# M1091A.net
KiCad netlist of a schematic drawn in EAGLE
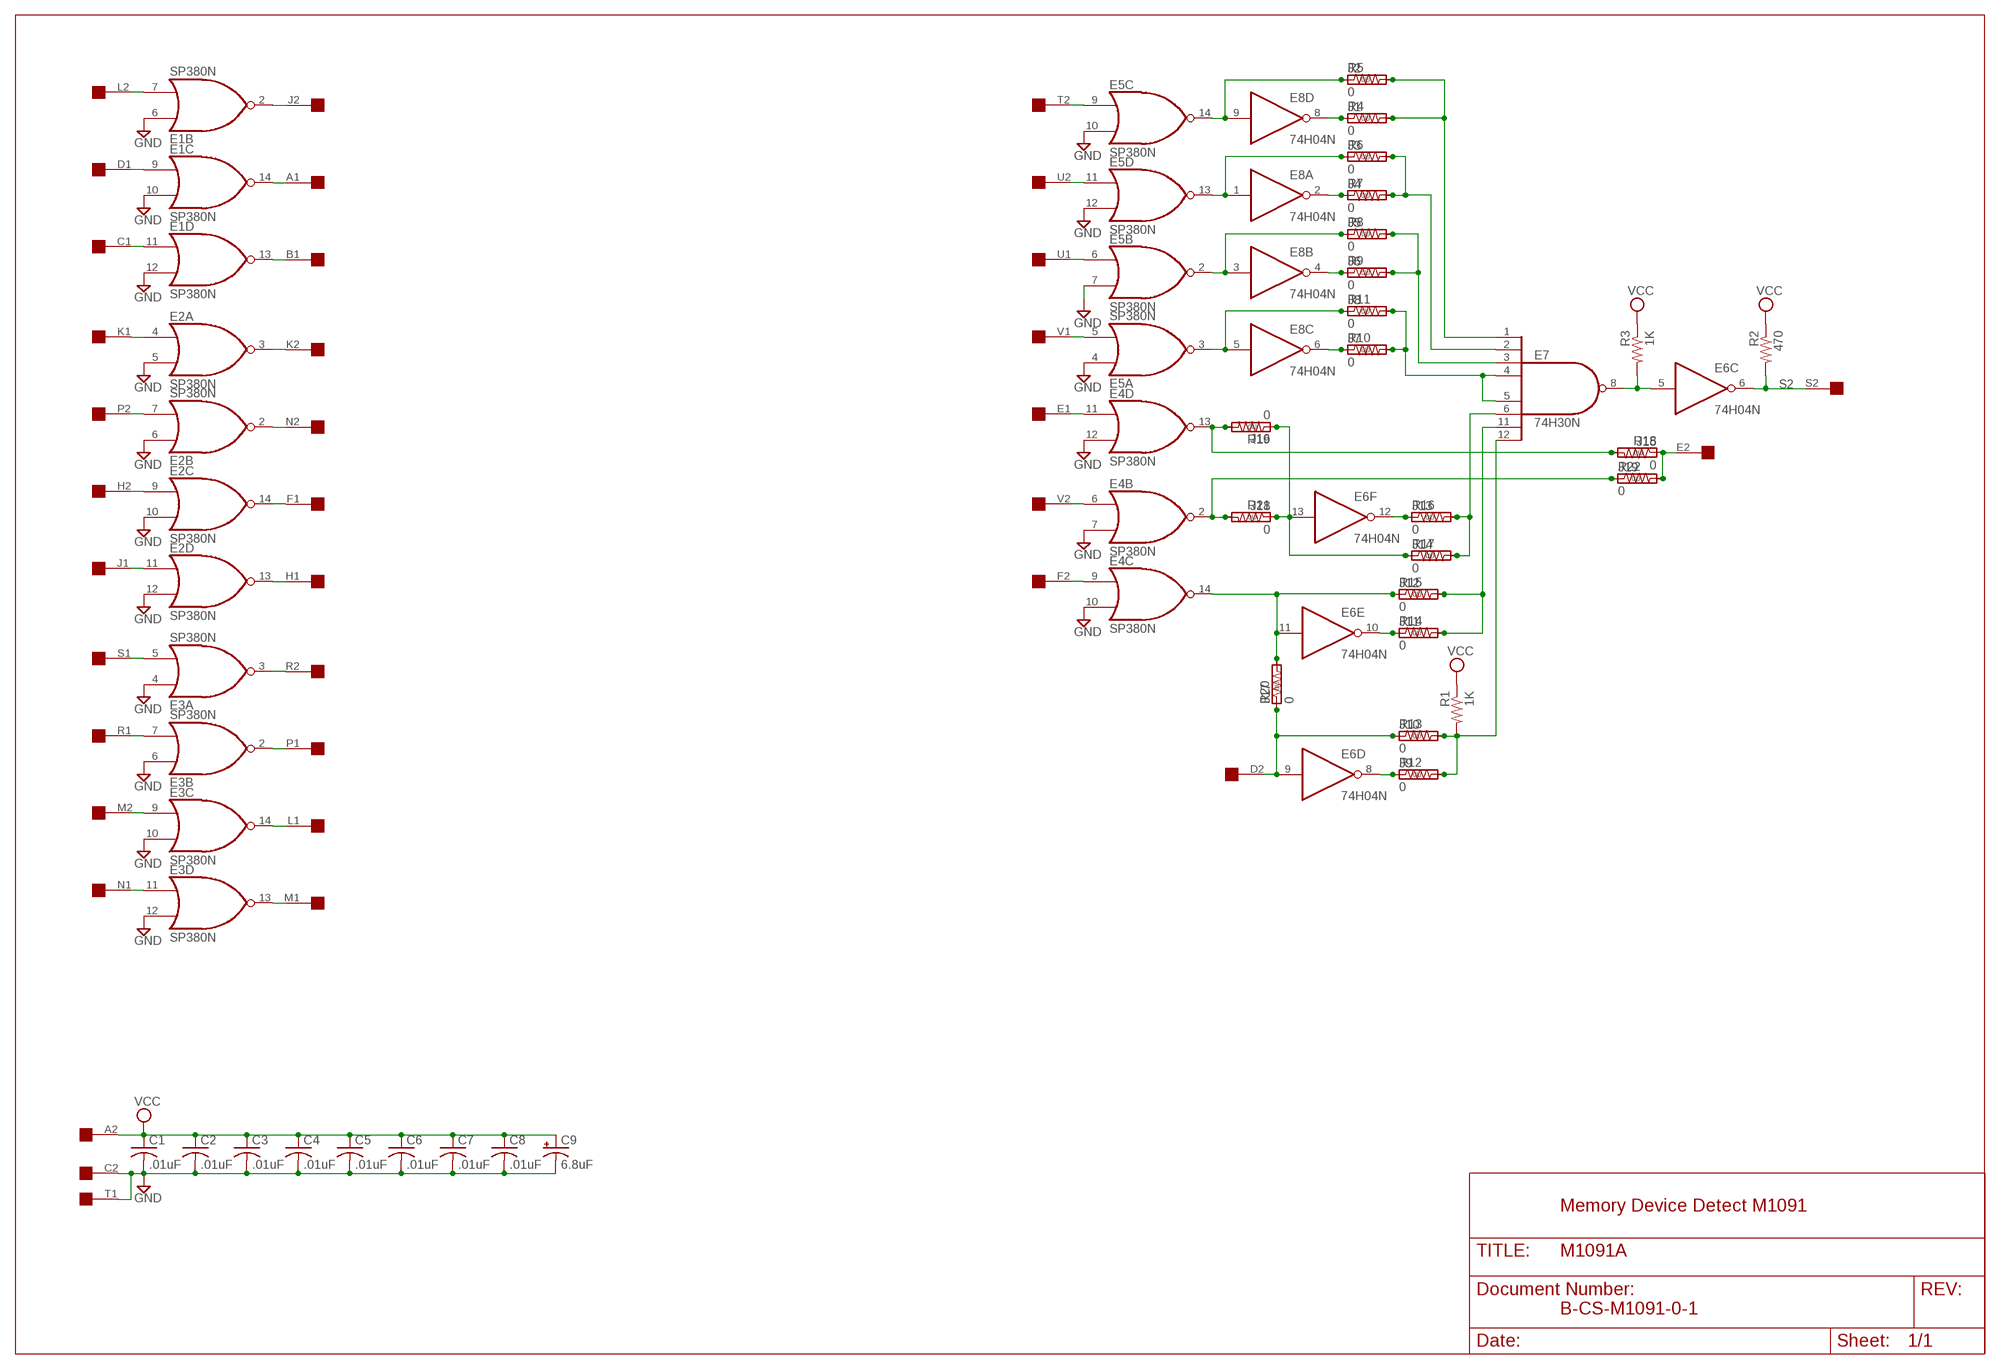
[diagram p0: schematic, sheet 1]

(export (version "E")
  (design (tool "Eeschema 10.0.6"))
  (components
    (comp (ref "C1")
      (value ".01uF")
      (footprint "eagle-import:C050-025X075")
      (libsource (lib "eagle-import") (part "C-US050-025X075"))
    )
    (comp (ref "C2")
      (value ".01uF")
      (footprint "eagle-import:C050-025X075")
      (libsource (lib "eagle-import") (part "C-US050-025X075"))
    )
    (comp (ref "C3")
      (value ".01uF")
      (footprint "eagle-import:C050-025X075")
      (libsource (lib "eagle-import") (part "C-US050-025X075"))
    )
    (comp (ref "C4")
      (value ".01uF")
      (footprint "eagle-import:C050-025X075")
      (libsource (lib "eagle-import") (part "C-US050-025X075"))
    )
    (comp (ref "C5")
      (value ".01uF")
      (footprint "eagle-import:C050-025X075")
      (libsource (lib "eagle-import") (part "C-US050-025X075"))
    )
    (comp (ref "C6")
      (value ".01uF")
      (footprint "eagle-import:C050-025X075")
      (libsource (lib "eagle-import") (part "C-US050-025X075"))
    )
    (comp (ref "C7")
      (value ".01uF")
      (footprint "eagle-import:C050-025X075")
      (libsource (lib "eagle-import") (part "C-US050-025X075"))
    )
    (comp (ref "C8")
      (value ".01uF")
      (footprint "eagle-import:C050-025X075")
      (libsource (lib "eagle-import") (part "C-US050-025X075"))
    )
    (comp (ref "C9")
      (value "6.8uF")
      (footprint "eagle-import:E12-8")
      (libsource (lib "eagle-import") (part "CPOL-USE20-8AXIAL"))
    )
    (comp (ref "E1")
      (value "SP380N")
      (footprint "eagle-import:DIL14")
      (libsource (lib "eagle-import") (part "SP380N"))
    )
    (comp (ref "E2")
      (value "SP380N")
      (footprint "eagle-import:DIL14")
      (libsource (lib "eagle-import") (part "SP380N"))
    )
    (comp (ref "E3")
      (value "SP380N")
      (footprint "eagle-import:DIL14")
      (libsource (lib "eagle-import") (part "SP380N"))
    )
    (comp (ref "E4")
      (value "SP380N")
      (footprint "eagle-import:DIL14")
      (libsource (lib "eagle-import") (part "SP380N"))
    )
    (comp (ref "E5")
      (value "SP380N")
      (footprint "eagle-import:DIL14")
      (libsource (lib "eagle-import") (part "SP380N"))
    )
    (comp (ref "E6")
      (value "74H04N")
      (footprint "eagle-import:DIL14")
      (libsource (lib "eagle-import") (part "7404NS"))
    )
    (comp (ref "E7")
      (value "74H30N")
      (footprint "eagle-import:DIL14")
      (libsource (lib "eagle-import") (part "7430NS"))
    )
    (comp (ref "E8")
      (value "74H04N")
      (footprint "eagle-import:DIL14")
      (libsource (lib "eagle-import") (part "7404NS"))
    )
    (comp (ref "J1")
      (value "0R")
      (footprint "eagle-import:0R_10")
      (libsource (lib "eagle-import") (part "0R"))
    )
    (comp (ref "J2")
      (value "0R")
      (footprint "eagle-import:0R_10")
      (libsource (lib "eagle-import") (part "0R"))
    )
    (comp (ref "J3")
      (value "0R")
      (footprint "eagle-import:0R_10")
      (libsource (lib "eagle-import") (part "0R"))
    )
    (comp (ref "J4")
      (value "0R")
      (footprint "eagle-import:0R_10")
      (libsource (lib "eagle-import") (part "0R"))
    )
    (comp (ref "J5")
      (value "0R")
      (footprint "eagle-import:0R_10")
      (libsource (lib "eagle-import") (part "0R"))
    )
    (comp (ref "J6")
      (value "0R")
      (footprint "eagle-import:0R_10")
      (libsource (lib "eagle-import") (part "0R"))
    )
    (comp (ref "J7")
      (value "0R")
      (footprint "eagle-import:0R_10")
      (libsource (lib "eagle-import") (part "0R"))
    )
    (comp (ref "J8")
      (value "0R")
      (footprint "eagle-import:0R_10")
      (libsource (lib "eagle-import") (part "0R"))
    )
    (comp (ref "J9")
      (value "0R")
      (footprint "eagle-import:0R_10")
      (libsource (lib "eagle-import") (part "0R"))
    )
    (comp (ref "J10")
      (value "0R")
      (footprint "eagle-import:0R_10")
      (libsource (lib "eagle-import") (part "0R"))
    )
    (comp (ref "J11")
      (value "0R")
      (footprint "eagle-import:0R_10")
      (libsource (lib "eagle-import") (part "0R"))
    )
    (comp (ref "J12")
      (value "0R")
      (footprint "eagle-import:0R_10")
      (libsource (lib "eagle-import") (part "0R"))
    )
    (comp (ref "J13")
      (value "0R")
      (footprint "eagle-import:0R_10")
      (libsource (lib "eagle-import") (part "0R"))
    )
    (comp (ref "J14")
      (value "0R")
      (footprint "eagle-import:0R_10")
      (libsource (lib "eagle-import") (part "0R"))
    )
    (comp (ref "J15")
      (value "0R")
      (footprint "eagle-import:0R_10")
      (libsource (lib "eagle-import") (part "0R"))
    )
    (comp (ref "J16")
      (value "0R")
      (footprint "eagle-import:0R_10")
      (libsource (lib "eagle-import") (part "0R"))
    )
    (comp (ref "J17")
      (value "0R")
      (footprint "eagle-import:0R_10")
      (libsource (lib "eagle-import") (part "0R"))
    )
    (comp (ref "J18")
      (value "0R")
      (footprint "eagle-import:0R_10")
      (libsource (lib "eagle-import") (part "0R"))
    )
    (comp (ref "J19")
      (value "0R")
      (footprint "eagle-import:0R_10")
      (libsource (lib "eagle-import") (part "0R"))
    )
    (comp (ref "R1")
      (value "1K")
      (footprint "eagle-import:0207_10")
      (libsource (lib "eagle-import") (part "R-US_0207/10"))
    )
    (comp (ref "R2")
      (value "470")
      (footprint "eagle-import:0207_10")
      (libsource (lib "eagle-import") (part "R-US_0207/10"))
    )
    (comp (ref "R3")
      (value "1K")
      (footprint "eagle-import:0207_10")
      (libsource (lib "eagle-import") (part "R-US_0207/10"))
    )
    (comp (ref "R4")
      (value "0")
      (footprint "eagle-import:0207_15")
      (libsource (lib "eagle-import") (part "R-US_0207/15"))
    )
    (comp (ref "R5")
      (value "0")
      (footprint "eagle-import:0207_15")
      (libsource (lib "eagle-import") (part "R-US_0207/15"))
    )
    (comp (ref "R6")
      (value "0")
      (footprint "eagle-import:0207_15")
      (libsource (lib "eagle-import") (part "R-US_0207/15"))
    )
    (comp (ref "R7")
      (value "0")
      (footprint "eagle-import:0207_15")
      (libsource (lib "eagle-import") (part "R-US_0207/15"))
    )
    (comp (ref "R8")
      (value "0")
      (footprint "eagle-import:0207_15")
      (libsource (lib "eagle-import") (part "R-US_0207/15"))
    )
    (comp (ref "R9")
      (value "0")
      (footprint "eagle-import:0207_15")
      (libsource (lib "eagle-import") (part "R-US_0207/15"))
    )
    (comp (ref "R10")
      (value "0")
      (footprint "eagle-import:0207_15")
      (libsource (lib "eagle-import") (part "R-US_0207/15"))
    )
    (comp (ref "R11")
      (value "0")
      (footprint "eagle-import:0207_15")
      (libsource (lib "eagle-import") (part "R-US_0207/15"))
    )
    (comp (ref "R12")
      (value "0")
      (footprint "eagle-import:0207_15")
      (libsource (lib "eagle-import") (part "R-US_0207/15"))
    )
    (comp (ref "R13")
      (value "0")
      (footprint "eagle-import:0207_15")
      (libsource (lib "eagle-import") (part "R-US_0207/15"))
    )
    (comp (ref "R14")
      (value "0")
      (footprint "eagle-import:0207_15")
      (libsource (lib "eagle-import") (part "R-US_0207/15"))
    )
    (comp (ref "R15")
      (value "0")
      (footprint "eagle-import:0207_15")
      (libsource (lib "eagle-import") (part "R-US_0207/15"))
    )
    (comp (ref "R16")
      (value "0")
      (footprint "eagle-import:0207_15")
      (libsource (lib "eagle-import") (part "R-US_0207/15"))
    )
    (comp (ref "R17")
      (value "0")
      (footprint "eagle-import:0207_15")
      (libsource (lib "eagle-import") (part "R-US_0207/15"))
    )
    (comp (ref "R18")
      (value "0")
      (footprint "eagle-import:0207_15")
      (libsource (lib "eagle-import") (part "R-US_0207/15"))
    )
    (comp (ref "R19")
      (value "0")
      (footprint "eagle-import:0207_15")
      (libsource (lib "eagle-import") (part "R-US_0207/15"))
    )
    (comp (ref "R20")
      (value "0")
      (footprint "eagle-import:0207_15")
      (libsource (lib "eagle-import") (part "R-US_0207/15"))
    )
    (comp (ref "R21")
      (value "0")
      (footprint "eagle-import:0207_15")
      (libsource (lib "eagle-import") (part "R-US_0207/15"))
    )
    (comp (ref "R22")
      (value "0")
      (footprint "eagle-import:0207_15")
      (libsource (lib "eagle-import") (part "R-US_0207/15"))
    )
    (comp (ref "U$2")
      (value "SINGLE")
      (footprint "eagle-import:EDGE-CON2")
      (libsource (lib "eagle-import") (part "SINGLE"))
    )
  )
  (nets
    (net (code "1") (name "/S2") (class "Default")
      (node (ref "E6") (pin "6") (pinfunction "O_6") (pintype "output"))
      (node (ref "R2") (pin "2") (pinfunction "2_2") (pintype "passive"))
      (node (ref "U$2") (pin "S2") (pinfunction "1_S2") (pintype "bidirectional"))
    )
    (net (code "2") (name "GND") (class "Default")
      (node (ref "C1") (pin "2") (pinfunction "2_2") (pintype "passive"))
      (node (ref "C2") (pin "2") (pinfunction "2_2") (pintype "passive"))
      (node (ref "C3") (pin "2") (pinfunction "2_2") (pintype "passive"))
      (node (ref "C4") (pin "2") (pinfunction "2_2") (pintype "passive"))
      (node (ref "C5") (pin "2") (pinfunction "2_2") (pintype "passive"))
      (node (ref "C6") (pin "2") (pinfunction "2_2") (pintype "passive"))
      (node (ref "C7") (pin "2") (pinfunction "2_2") (pintype "passive"))
      (node (ref "C8") (pin "2") (pinfunction "2_2") (pintype "passive"))
      (node (ref "C9") (pin "-") (pinfunction "-_-") (pintype "passive"))
      (node (ref "E1") (pin "10") (pinfunction "I1_10") (pintype "input"))
      (node (ref "E1") (pin "12") (pinfunction "I1_12") (pintype "input"))
      (node (ref "E1") (pin "6") (pinfunction "I0_6") (pintype "input"))
      (node (ref "E2") (pin "10") (pinfunction "I1_10") (pintype "input"))
      (node (ref "E2") (pin "12") (pinfunction "I1_12") (pintype "input"))
      (node (ref "E2") (pin "5") (pinfunction "I1_5") (pintype "input"))
      (node (ref "E2") (pin "6") (pinfunction "I0_6") (pintype "input"))
      (node (ref "E3") (pin "10") (pinfunction "I1_10") (pintype "input"))
      (node (ref "E3") (pin "12") (pinfunction "I1_12") (pintype "input"))
      (node (ref "E3") (pin "4") (pinfunction "I0_4") (pintype "input"))
      (node (ref "E3") (pin "6") (pinfunction "I0_6") (pintype "input"))
      (node (ref "E4") (pin "10") (pinfunction "I1_10") (pintype "input"))
      (node (ref "E4") (pin "12") (pinfunction "I1_12") (pintype "input"))
      (node (ref "E4") (pin "7") (pinfunction "I1_7") (pintype "input"))
      (node (ref "E5") (pin "10") (pinfunction "I1_10") (pintype "input"))
      (node (ref "E5") (pin "12") (pinfunction "I1_12") (pintype "input"))
      (node (ref "E5") (pin "4") (pinfunction "I0_4") (pintype "input"))
      (node (ref "E5") (pin "7") (pinfunction "I1_7") (pintype "input"))
      (node (ref "U$2") (pin "C2") (pinfunction "1_C2") (pintype "bidirectional"))
      (node (ref "U$2") (pin "T1") (pinfunction "1_T1") (pintype "bidirectional"))
    )
    (net (code "3") (name "Net-(E1B-I1)") (class "Default")
      (node (ref "E1") (pin "7") (pinfunction "I1_7") (pintype "input"))
      (node (ref "U$2") (pin "L2") (pinfunction "1_L2") (pintype "bidirectional"))
    )
    (net (code "4") (name "Net-(E1B-O)") (class "Default")
      (node (ref "E1") (pin "2") (pinfunction "O_2") (pintype "output"))
      (node (ref "U$2") (pin "J2") (pinfunction "1_J2") (pintype "bidirectional"))
    )
    (net (code "5") (name "Net-(E1C-I0)") (class "Default")
      (node (ref "E1") (pin "9") (pinfunction "I0_9") (pintype "input"))
      (node (ref "U$2") (pin "D1") (pinfunction "1_D1") (pintype "bidirectional"))
    )
    (net (code "6") (name "Net-(E1C-O)") (class "Default")
      (node (ref "E1") (pin "14") (pinfunction "O_14") (pintype "output"))
      (node (ref "U$2") (pin "A1") (pinfunction "1_A1") (pintype "bidirectional"))
    )
    (net (code "7") (name "Net-(E1D-I0)") (class "Default")
      (node (ref "E1") (pin "11") (pinfunction "I0_11") (pintype "input"))
      (node (ref "U$2") (pin "C1") (pinfunction "1_C1") (pintype "bidirectional"))
    )
    (net (code "8") (name "Net-(E1D-O)") (class "Default")
      (node (ref "E1") (pin "13") (pinfunction "O_13") (pintype "output"))
      (node (ref "U$2") (pin "B1") (pinfunction "1_B1") (pintype "bidirectional"))
    )
    (net (code "9") (name "Net-(E2A-I0)") (class "Default")
      (node (ref "E2") (pin "4") (pinfunction "I0_4") (pintype "input"))
      (node (ref "U$2") (pin "K1") (pinfunction "1_K1") (pintype "bidirectional"))
    )
    (net (code "10") (name "Net-(E2A-O)") (class "Default")
      (node (ref "E2") (pin "3") (pinfunction "O_3") (pintype "output"))
      (node (ref "U$2") (pin "K2") (pinfunction "1_K2") (pintype "bidirectional"))
    )
    (net (code "11") (name "Net-(E2B-I1)") (class "Default")
      (node (ref "E2") (pin "7") (pinfunction "I1_7") (pintype "input"))
      (node (ref "U$2") (pin "P2") (pinfunction "1_P2") (pintype "bidirectional"))
    )
    (net (code "12") (name "Net-(E2B-O)") (class "Default")
      (node (ref "E2") (pin "2") (pinfunction "O_2") (pintype "output"))
      (node (ref "U$2") (pin "N2") (pinfunction "1_N2") (pintype "bidirectional"))
    )
    (net (code "13") (name "Net-(E2C-I0)") (class "Default")
      (node (ref "E2") (pin "9") (pinfunction "I0_9") (pintype "input"))
      (node (ref "U$2") (pin "H2") (pinfunction "1_H2") (pintype "bidirectional"))
    )
    (net (code "14") (name "Net-(E2C-O)") (class "Default")
      (node (ref "E2") (pin "14") (pinfunction "O_14") (pintype "output"))
      (node (ref "U$2") (pin "F1") (pinfunction "1_F1") (pintype "bidirectional"))
    )
    (net (code "15") (name "Net-(E2D-I0)") (class "Default")
      (node (ref "E2") (pin "11") (pinfunction "I0_11") (pintype "input"))
      (node (ref "U$2") (pin "J1") (pinfunction "1_J1") (pintype "bidirectional"))
    )
    (net (code "16") (name "Net-(E2D-O)") (class "Default")
      (node (ref "E2") (pin "13") (pinfunction "O_13") (pintype "output"))
      (node (ref "U$2") (pin "H1") (pinfunction "1_H1") (pintype "bidirectional"))
    )
    (net (code "17") (name "Net-(E3A-I1)") (class "Default")
      (node (ref "E3") (pin "5") (pinfunction "I1_5") (pintype "input"))
      (node (ref "U$2") (pin "S1") (pinfunction "1_S1") (pintype "bidirectional"))
    )
    (net (code "18") (name "Net-(E3A-O)") (class "Default")
      (node (ref "E3") (pin "3") (pinfunction "O_3") (pintype "output"))
      (node (ref "U$2") (pin "R2") (pinfunction "1_R2") (pintype "bidirectional"))
    )
    (net (code "19") (name "Net-(E3B-I1)") (class "Default")
      (node (ref "E3") (pin "7") (pinfunction "I1_7") (pintype "input"))
      (node (ref "U$2") (pin "R1") (pinfunction "1_R1") (pintype "bidirectional"))
    )
    (net (code "20") (name "Net-(E3B-O)") (class "Default")
      (node (ref "E3") (pin "2") (pinfunction "O_2") (pintype "output"))
      (node (ref "U$2") (pin "P1") (pinfunction "1_P1") (pintype "bidirectional"))
    )
    (net (code "21") (name "Net-(E3C-I0)") (class "Default")
      (node (ref "E3") (pin "9") (pinfunction "I0_9") (pintype "input"))
      (node (ref "U$2") (pin "M2") (pinfunction "1_M2") (pintype "bidirectional"))
    )
    (net (code "22") (name "Net-(E3C-O)") (class "Default")
      (node (ref "E3") (pin "14") (pinfunction "O_14") (pintype "output"))
      (node (ref "U$2") (pin "L1") (pinfunction "1_L1") (pintype "bidirectional"))
    )
    (net (code "23") (name "Net-(E3D-I0)") (class "Default")
      (node (ref "E3") (pin "11") (pinfunction "I0_11") (pintype "input"))
      (node (ref "U$2") (pin "N1") (pinfunction "1_N1") (pintype "bidirectional"))
    )
    (net (code "24") (name "Net-(E3D-O)") (class "Default")
      (node (ref "E3") (pin "13") (pinfunction "O_13") (pintype "output"))
      (node (ref "U$2") (pin "M1") (pinfunction "1_M1") (pintype "bidirectional"))
    )
    (net (code "25") (name "Net-(E4B-I0)") (class "Default")
      (node (ref "E4") (pin "6") (pinfunction "I0_6") (pintype "input"))
      (node (ref "U$2") (pin "V2") (pinfunction "1_V2") (pintype "bidirectional"))
    )
    (net (code "26") (name "Net-(E4B-O)") (class "Default")
      (node (ref "E4") (pin "2") (pinfunction "O_2") (pintype "output"))
      (node (ref "J18") (pin "2") (pinfunction "2_2") (pintype "passive"))
      (node (ref "J19") (pin "1") (pinfunction "1_1") (pintype "passive"))
      (node (ref "R21") (pin "2") (pinfunction "2_2") (pintype "passive"))
      (node (ref "R22") (pin "1") (pinfunction "1_1") (pintype "passive"))
    )
    (net (code "27") (name "Net-(E4C-I0)") (class "Default")
      (node (ref "E4") (pin "9") (pinfunction "I0_9") (pintype "input"))
      (node (ref "U$2") (pin "F2") (pinfunction "1_F2") (pintype "bidirectional"))
    )
    (net (code "28") (name "Net-(E4C-O)") (class "Default")
      (node (ref "E4") (pin "14") (pinfunction "O_14") (pintype "output"))
      (node (ref "E6") (pin "11") (pinfunction "I_11") (pintype "input"))
      (node (ref "J12") (pin "1") (pinfunction "1_1") (pintype "passive"))
      (node (ref "J17") (pin "2") (pinfunction "2_2") (pintype "passive"))
      (node (ref "R15") (pin "1") (pinfunction "1_1") (pintype "passive"))
      (node (ref "R20") (pin "2") (pinfunction "2_2") (pintype "passive"))
    )
    (net (code "29") (name "Net-(E4D-I0)") (class "Default")
      (node (ref "E4") (pin "11") (pinfunction "I0_11") (pintype "input"))
      (node (ref "U$2") (pin "E1") (pinfunction "1_E1") (pintype "bidirectional"))
    )
    (net (code "30") (name "Net-(E4D-O)") (class "Default")
      (node (ref "E4") (pin "13") (pinfunction "O_13") (pintype "output"))
      (node (ref "J15") (pin "2") (pinfunction "2_2") (pintype "passive"))
      (node (ref "J16") (pin "2") (pinfunction "2_2") (pintype "passive"))
      (node (ref "R18") (pin "2") (pinfunction "2_2") (pintype "passive"))
      (node (ref "R19") (pin "2") (pinfunction "2_2") (pintype "passive"))
    )
    (net (code "31") (name "Net-(E5A-I1)") (class "Default")
      (node (ref "E5") (pin "5") (pinfunction "I1_5") (pintype "input"))
      (node (ref "U$2") (pin "V1") (pinfunction "1_V1") (pintype "bidirectional"))
    )
    (net (code "32") (name "Net-(E5A-O)") (class "Default")
      (node (ref "E5") (pin "3") (pinfunction "O_3") (pintype "output"))
      (node (ref "E8") (pin "5") (pinfunction "I_5") (pintype "input"))
      (node (ref "J8") (pin "1") (pinfunction "1_1") (pintype "passive"))
      (node (ref "R11") (pin "1") (pinfunction "1_1") (pintype "passive"))
    )
    (net (code "33") (name "Net-(E5B-I0)") (class "Default")
      (node (ref "E5") (pin "6") (pinfunction "I0_6") (pintype "input"))
      (node (ref "U$2") (pin "U1") (pinfunction "1_U1") (pintype "bidirectional"))
    )
    (net (code "34") (name "Net-(E5B-O)") (class "Default")
      (node (ref "E5") (pin "2") (pinfunction "O_2") (pintype "output"))
      (node (ref "E8") (pin "3") (pinfunction "I_3") (pintype "input"))
      (node (ref "J5") (pin "1") (pinfunction "1_1") (pintype "passive"))
      (node (ref "R8") (pin "1") (pinfunction "1_1") (pintype "passive"))
    )
    (net (code "35") (name "Net-(E5C-I0)") (class "Default")
      (node (ref "E5") (pin "9") (pinfunction "I0_9") (pintype "input"))
      (node (ref "U$2") (pin "T2") (pinfunction "1_T2") (pintype "bidirectional"))
    )
    (net (code "36") (name "Net-(E5C-O)") (class "Default")
      (node (ref "E5") (pin "14") (pinfunction "O_14") (pintype "output"))
      (node (ref "E8") (pin "9") (pinfunction "I_9") (pintype "input"))
      (node (ref "J2") (pin "1") (pinfunction "1_1") (pintype "passive"))
      (node (ref "R5") (pin "1") (pinfunction "1_1") (pintype "passive"))
    )
    (net (code "37") (name "Net-(E5D-I0)") (class "Default")
      (node (ref "E5") (pin "11") (pinfunction "I0_11") (pintype "input"))
      (node (ref "U$2") (pin "U2") (pinfunction "1_U2") (pintype "bidirectional"))
    )
    (net (code "38") (name "Net-(E5D-O)") (class "Default")
      (node (ref "E5") (pin "13") (pinfunction "O_13") (pintype "output"))
      (node (ref "E8") (pin "1") (pinfunction "I_1") (pintype "input"))
      (node (ref "J3") (pin "1") (pinfunction "1_1") (pintype "passive"))
      (node (ref "R6") (pin "1") (pinfunction "1_1") (pintype "passive"))
    )
    (net (code "39") (name "Net-(E6C-I)") (class "Default")
      (node (ref "E6") (pin "5") (pinfunction "I_5") (pintype "input"))
      (node (ref "E7") (pin "8") (pinfunction "O_8") (pintype "output"))
      (node (ref "R3") (pin "2") (pinfunction "2_2") (pintype "passive"))
    )
    (net (code "40") (name "Net-(E6D-I)") (class "Default")
      (node (ref "E6") (pin "9") (pinfunction "I_9") (pintype "input"))
      (node (ref "J10") (pin "1") (pinfunction "1_1") (pintype "passive"))
      (node (ref "J17") (pin "1") (pinfunction "1_1") (pintype "passive"))
      (node (ref "R13") (pin "1") (pinfunction "1_1") (pintype "passive"))
      (node (ref "R20") (pin "1") (pinfunction "1_1") (pintype "passive"))
      (node (ref "U$2") (pin "D2") (pinfunction "1_D2") (pintype "bidirectional"))
    )
    (net (code "41") (name "Net-(E6D-O)") (class "Default")
      (node (ref "E6") (pin "8") (pinfunction "O_8") (pintype "output"))
      (node (ref "J9") (pin "1") (pinfunction "1_1") (pintype "passive"))
      (node (ref "R12") (pin "1") (pinfunction "1_1") (pintype "passive"))
    )
    (net (code "42") (name "Net-(E6E-O)") (class "Default")
      (node (ref "E6") (pin "10") (pinfunction "O_10") (pintype "output"))
      (node (ref "J11") (pin "1") (pinfunction "1_1") (pintype "passive"))
      (node (ref "R14") (pin "1") (pinfunction "1_1") (pintype "passive"))
    )
    (net (code "43") (name "Net-(E6F-I)") (class "Default")
      (node (ref "E6") (pin "13") (pinfunction "I_13") (pintype "input"))
      (node (ref "J14") (pin "1") (pinfunction "1_1") (pintype "passive"))
      (node (ref "J16") (pin "1") (pinfunction "1_1") (pintype "passive"))
      (node (ref "J18") (pin "1") (pinfunction "1_1") (pintype "passive"))
      (node (ref "R17") (pin "1") (pinfunction "1_1") (pintype "passive"))
      (node (ref "R19") (pin "1") (pinfunction "1_1") (pintype "passive"))
      (node (ref "R21") (pin "1") (pinfunction "1_1") (pintype "passive"))
    )
    (net (code "44") (name "Net-(E6F-O)") (class "Default")
      (node (ref "E6") (pin "12") (pinfunction "O_12") (pintype "output"))
      (node (ref "J13") (pin "1") (pinfunction "1_1") (pintype "passive"))
      (node (ref "R16") (pin "1") (pinfunction "1_1") (pintype "passive"))
    )
    (net (code "45") (name "Net-(E7D-I0)") (class "Default")
      (node (ref "E7") (pin "1") (pinfunction "I0_1") (pintype "input"))
      (node (ref "J1") (pin "2") (pinfunction "2_2") (pintype "passive"))
      (node (ref "J2") (pin "2") (pinfunction "2_2") (pintype "passive"))
      (node (ref "R4") (pin "2") (pinfunction "2_2") (pintype "passive"))
      (node (ref "R5") (pin "2") (pinfunction "2_2") (pintype "passive"))
    )
    (net (code "46") (name "Net-(E7D-I1)") (class "Default")
      (node (ref "E7") (pin "2") (pinfunction "I1_2") (pintype "input"))
      (node (ref "J3") (pin "2") (pinfunction "2_2") (pintype "passive"))
      (node (ref "J4") (pin "2") (pinfunction "2_2") (pintype "passive"))
      (node (ref "R6") (pin "2") (pinfunction "2_2") (pintype "passive"))
      (node (ref "R7") (pin "2") (pinfunction "2_2") (pintype "passive"))
    )
    (net (code "47") (name "Net-(E7D-I2)") (class "Default")
      (node (ref "E7") (pin "3") (pinfunction "I2_3") (pintype "input"))
      (node (ref "J5") (pin "2") (pinfunction "2_2") (pintype "passive"))
      (node (ref "J6") (pin "2") (pinfunction "2_2") (pintype "passive"))
      (node (ref "R8") (pin "2") (pinfunction "2_2") (pintype "passive"))
      (node (ref "R9") (pin "2") (pinfunction "2_2") (pintype "passive"))
    )
    (net (code "48") (name "Net-(E7D-I3)") (class "Default")
      (node (ref "E7") (pin "4") (pinfunction "I3_4") (pintype "input"))
      (node (ref "E7") (pin "5") (pinfunction "I4_5") (pintype "input"))
      (node (ref "J7") (pin "2") (pinfunction "2_2") (pintype "passive"))
      (node (ref "J8") (pin "2") (pinfunction "2_2") (pintype "passive"))
      (node (ref "R10") (pin "2") (pinfunction "2_2") (pintype "passive"))
      (node (ref "R11") (pin "2") (pinfunction "2_2") (pintype "passive"))
    )
    (net (code "49") (name "Net-(E7D-I5)") (class "Default")
      (node (ref "E7") (pin "6") (pinfunction "I5_6") (pintype "input"))
      (node (ref "J13") (pin "2") (pinfunction "2_2") (pintype "passive"))
      (node (ref "J14") (pin "2") (pinfunction "2_2") (pintype "passive"))
      (node (ref "R16") (pin "2") (pinfunction "2_2") (pintype "passive"))
      (node (ref "R17") (pin "2") (pinfunction "2_2") (pintype "passive"))
    )
    (net (code "50") (name "Net-(E7D-I6)") (class "Default")
      (node (ref "E7") (pin "11") (pinfunction "I6_11") (pintype "input"))
      (node (ref "J11") (pin "2") (pinfunction "2_2") (pintype "passive"))
      (node (ref "J12") (pin "2") (pinfunction "2_2") (pintype "passive"))
      (node (ref "R14") (pin "2") (pinfunction "2_2") (pintype "passive"))
      (node (ref "R15") (pin "2") (pinfunction "2_2") (pintype "passive"))
    )
    (net (code "51") (name "Net-(E7D-I7)") (class "Default")
      (node (ref "E7") (pin "12") (pinfunction "I7_12") (pintype "input"))
      (node (ref "J10") (pin "2") (pinfunction "2_2") (pintype "passive"))
      (node (ref "J9") (pin "2") (pinfunction "2_2") (pintype "passive"))
      (node (ref "R1") (pin "2") (pinfunction "2_2") (pintype "passive"))
      (node (ref "R12") (pin "2") (pinfunction "2_2") (pintype "passive"))
      (node (ref "R13") (pin "2") (pinfunction "2_2") (pintype "passive"))
    )
    (net (code "52") (name "Net-(E8A-O)") (class "Default")
      (node (ref "E8") (pin "2") (pinfunction "O_2") (pintype "output"))
      (node (ref "J4") (pin "1") (pinfunction "1_1") (pintype "passive"))
      (node (ref "R7") (pin "1") (pinfunction "1_1") (pintype "passive"))
    )
    (net (code "53") (name "Net-(E8B-O)") (class "Default")
      (node (ref "E8") (pin "4") (pinfunction "O_4") (pintype "output"))
      (node (ref "J6") (pin "1") (pinfunction "1_1") (pintype "passive"))
      (node (ref "R9") (pin "1") (pinfunction "1_1") (pintype "passive"))
    )
    (net (code "54") (name "Net-(E8C-O)") (class "Default")
      (node (ref "E8") (pin "6") (pinfunction "O_6") (pintype "output"))
      (node (ref "J7") (pin "1") (pinfunction "1_1") (pintype "passive"))
      (node (ref "R10") (pin "1") (pinfunction "1_1") (pintype "passive"))
    )
    (net (code "55") (name "Net-(E8D-O)") (class "Default")
      (node (ref "E8") (pin "8") (pinfunction "O_8") (pintype "output"))
      (node (ref "J1") (pin "1") (pinfunction "1_1") (pintype "passive"))
      (node (ref "R4") (pin "1") (pinfunction "1_1") (pintype "passive"))
    )
    (net (code "56") (name "Net-(U$2J-1)") (class "Default")
      (node (ref "J15") (pin "1") (pinfunction "1_1") (pintype "passive"))
      (node (ref "J19") (pin "2") (pinfunction "2_2") (pintype "passive"))
      (node (ref "R18") (pin "1") (pinfunction "1_1") (pintype "passive"))
      (node (ref "R22") (pin "2") (pinfunction "2_2") (pintype "passive"))
      (node (ref "U$2") (pin "E2") (pinfunction "1_E2") (pintype "bidirectional"))
    )
    (net (code "57") (name "VCC") (class "Default")
      (node (ref "C1") (pin "1") (pinfunction "1_1") (pintype "passive"))
      (node (ref "C2") (pin "1") (pinfunction "1_1") (pintype "passive"))
      (node (ref "C3") (pin "1") (pinfunction "1_1") (pintype "passive"))
      (node (ref "C4") (pin "1") (pinfunction "1_1") (pintype "passive"))
      (node (ref "C5") (pin "1") (pinfunction "1_1") (pintype "passive"))
      (node (ref "C6") (pin "1") (pinfunction "1_1") (pintype "passive"))
      (node (ref "C7") (pin "1") (pinfunction "1_1") (pintype "passive"))
      (node (ref "C8") (pin "1") (pinfunction "1_1") (pintype "passive"))
      (node (ref "C9") (pin "+") (pinfunction "+_+") (pintype "passive"))
      (node (ref "R1") (pin "1") (pinfunction "1_1") (pintype "passive"))
      (node (ref "R2") (pin "1") (pinfunction "1_1") (pintype "passive"))
      (node (ref "R3") (pin "1") (pinfunction "1_1") (pintype "passive"))
      (node (ref "U$2") (pin "A2") (pinfunction "1_A2") (pintype "bidirectional"))
    )
  )
)
